# logic.net
KiCad netlist of a schematic drawn in Altium Designer
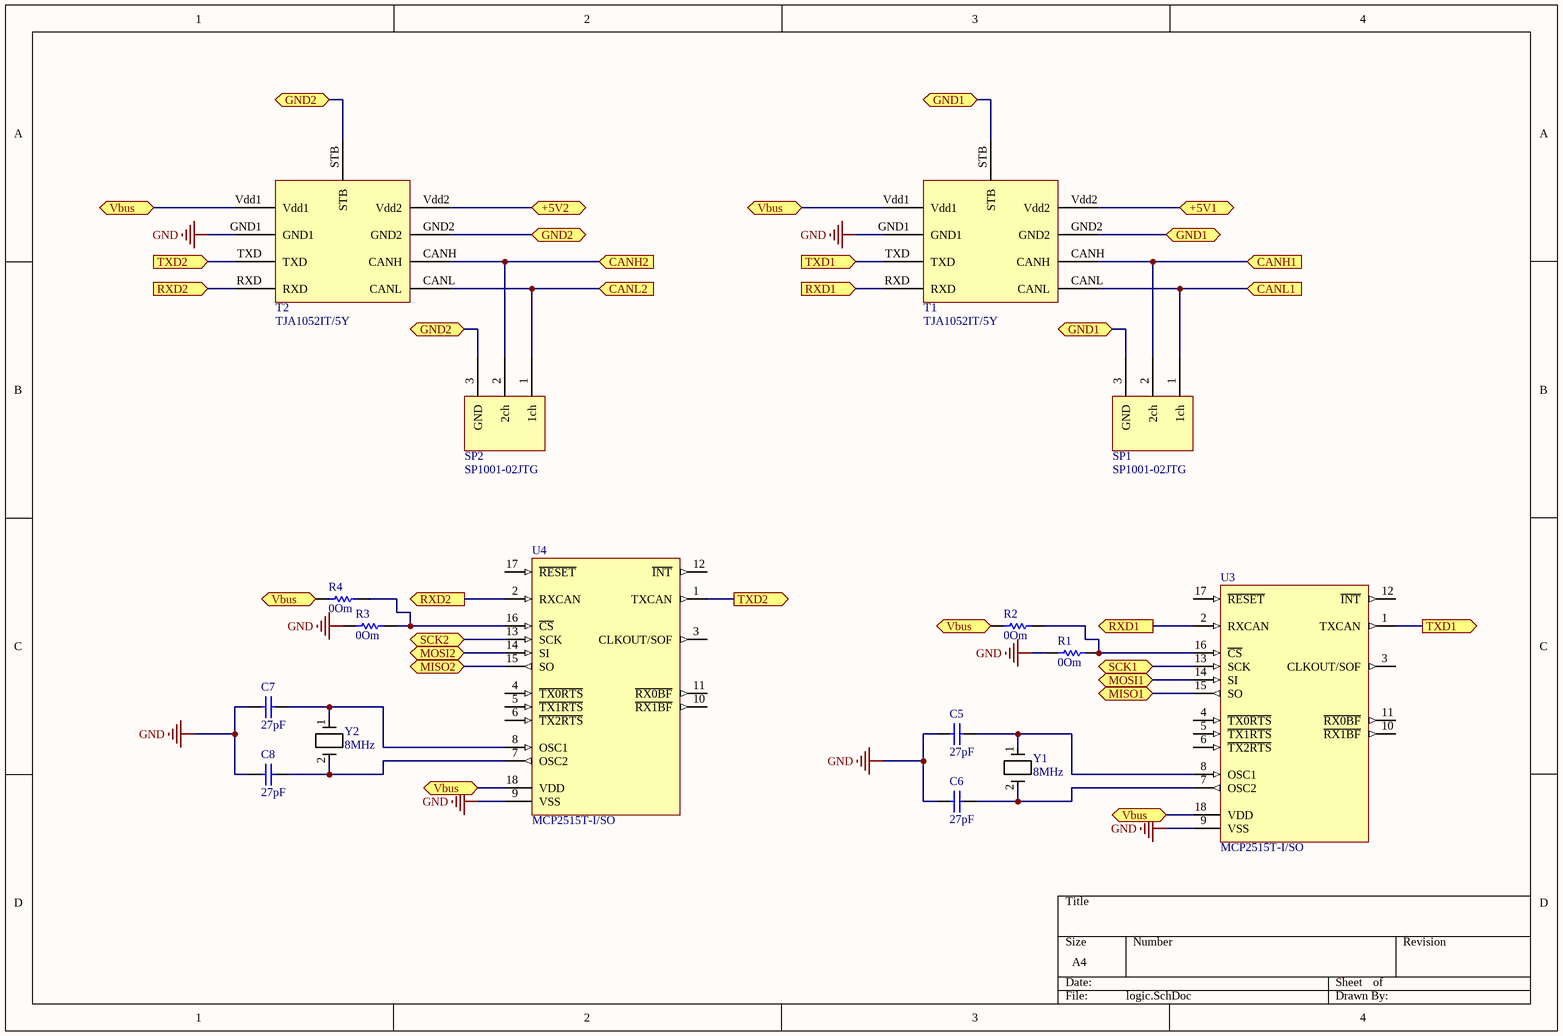
[diagram p0: logic.SchDoc]

(export (version "E")
  (design (tool "Eeschema 10.0.6"))
  (components
    (comp (ref "C5")
      (value "27pF")
      (footprint "CAPC1608X90X35ML10T15")
      (fields (field (name "MANUFACTURER") "Murata") (field (name "PART NUMBER") "GCM1885C2A101JA16D"))
      (libsource (lib "Altium Content Vault") (part "CAP"))
    )
    (comp (ref "C6")
      (value "27pF")
      (footprint "CAPC1608X90X35ML10T15")
      (fields (field (name "MANUFACTURER") "Murata") (field (name "PART NUMBER") "GCM1885C2A101JA16D"))
      (libsource (lib "Altium Content Vault") (part "CAP"))
    )
    (comp (ref "C7")
      (value "27pF")
      (footprint "CAPC1608X90X35ML10T15")
      (fields (field (name "MANUFACTURER") "Murata") (field (name "PART NUMBER") "GCM1885C2A101JA16D"))
      (libsource (lib "Altium Content Vault") (part "CAP"))
    )
    (comp (ref "C8")
      (value "27pF")
      (footprint "CAPC1608X90X35ML10T15")
      (fields (field (name "MANUFACTURER") "Murata") (field (name "PART NUMBER") "GCM1885C2A101JA16D"))
      (libsource (lib "Altium Content Vault") (part "CAP"))
    )
    (comp (ref "R1")
      (value "0Om")
      (footprint "RESC1608X55X30ML20T10")
      (fields (field (name "PART NUMBER") "RK73H1JTTD5101F") (field (name "MANUFACTURER") "KOA Speer"))
      (libsource (lib "Altium Content Vault") (part "RES"))
    )
    (comp (ref "R2")
      (value "0Om")
      (footprint "RESC1608X55X30ML20T10")
      (fields (field (name "PART NUMBER") "RK73H1JTTD5101F") (field (name "MANUFACTURER") "KOA Speer"))
      (libsource (lib "Altium Content Vault") (part "RES"))
    )
    (comp (ref "R3")
      (value "0Om")
      (footprint "RESC1608X55X30ML20T10")
      (fields (field (name "PART NUMBER") "RK73H1JTTD5101F") (field (name "MANUFACTURER") "KOA Speer"))
      (libsource (lib "Altium Content Vault") (part "RES"))
    )
    (comp (ref "R4")
      (value "0Om")
      (footprint "RESC1608X55X30ML20T10")
      (fields (field (name "PART NUMBER") "RK73H1JTTD5101F") (field (name "MANUFACTURER") "KOA Speer"))
      (libsource (lib "Altium Content Vault") (part "RES"))
    )
    (comp (ref "SP1")
      (value "SP1001-02JTG")
      (footprint "SC70-3")
      (libsource (lib "lib") (part "SP1001-02JTG"))
    )
    (comp (ref "SP2")
      (value "SP1001-02JTG")
      (footprint "SC70-3")
      (libsource (lib "lib") (part "SP1001-02JTG"))
    )
    (comp (ref "T1")
      (value "TJA1052IT/5Y")
      (footprint "TJA1052")
      (libsource (lib "lib") (part "TJA1052IT/5Y"))
    )
    (comp (ref "T2")
      (value "TJA1052IT/5Y")
      (footprint "TJA1052")
      (libsource (lib "lib") (part "TJA1052IT/5Y"))
    )
    (comp (ref "U3")
      (value "MCP2515T-I/SO")
      (footprint "SOIC-SO18_N")
      (description "Stand-Alone CAN Controller With SPI Interface, 18-Pin SOIC, Industrial Temperature, Tape and Reel")
      (libsource (lib "Altium Content Vault") (part "COM-CAN-MCP2515-18"))
    )
    (comp (ref "U4")
      (value "MCP2515T-I/SO")
      (footprint "SOIC-SO18_N")
      (description "Stand-Alone CAN Controller With SPI Interface, 18-Pin SOIC, Industrial Temperature, Tape and Reel")
      (libsource (lib "Altium Content Vault") (part "COM-CAN-MCP2515-18"))
    )
    (comp (ref "Y1")
      (value "8MHz")
      (footprint "SMD-5032_2P")
      (libsource (lib "lib") (part "SMD-5032_2P resonator"))
    )
    (comp (ref "Y2")
      (value "8MHz")
      (footprint "SMD-5032_2P")
      (libsource (lib "lib") (part "SMD-5032_2P resonator"))
    )
  )
  (nets
    (net (code "1") (name "/+5V1") (class "Default")
      (node (ref "T1") (pin "Vdd2") (pinfunction "Vdd2_Vdd2") (pintype "passive"))
    )
    (net (code "2") (name "/+5V2") (class "Default")
      (node (ref "T2") (pin "Vdd2") (pinfunction "Vdd2_Vdd2") (pintype "passive"))
    )
    (net (code "3") (name "/CANH1") (class "Default")
      (node (ref "SP1") (pin "2") (pinfunction "2ch_2") (pintype "passive"))
      (node (ref "T1") (pin "CANH") (pinfunction "CANH_CANH") (pintype "passive"))
    )
    (net (code "4") (name "/CANH2") (class "Default")
      (node (ref "SP2") (pin "2") (pinfunction "2ch_2") (pintype "passive"))
      (node (ref "T2") (pin "CANH") (pinfunction "CANH_CANH") (pintype "passive"))
    )
    (net (code "5") (name "/CANL1") (class "Default")
      (node (ref "SP1") (pin "1") (pinfunction "1ch_1") (pintype "passive"))
      (node (ref "T1") (pin "CANL") (pinfunction "CANL_CANL") (pintype "passive"))
    )
    (net (code "6") (name "/CANL2") (class "Default")
      (node (ref "SP2") (pin "1") (pinfunction "1ch_1") (pintype "passive"))
      (node (ref "T2") (pin "CANL") (pinfunction "CANL_CANL") (pintype "passive"))
    )
    (net (code "7") (name "/GND1") (class "Default")
      (node (ref "SP1") (pin "3") (pinfunction "GND_3") (pintype "passive"))
      (node (ref "T1") (pin "GND2") (pinfunction "GND2_GND2") (pintype "passive"))
      (node (ref "T1") (pin "STB") (pinfunction "STB_STB") (pintype "passive"))
    )
    (net (code "8") (name "/GND2") (class "Default")
      (node (ref "SP2") (pin "3") (pinfunction "GND_3") (pintype "passive"))
      (node (ref "T2") (pin "GND2") (pinfunction "GND2_GND2") (pintype "passive"))
      (node (ref "T2") (pin "STB") (pinfunction "STB_STB") (pintype "passive"))
    )
    (net (code "9") (name "/MISO1") (class "Default")
      (node (ref "U3") (pin "15") (pinfunction "SO_15") (pintype "output"))
    )
    (net (code "10") (name "/MISO2") (class "Default")
      (node (ref "U4") (pin "15") (pinfunction "SO_15") (pintype "output"))
    )
    (net (code "11") (name "/MOSI1") (class "Default")
      (node (ref "U3") (pin "14") (pinfunction "SI_14") (pintype "input"))
    )
    (net (code "12") (name "/MOSI2") (class "Default")
      (node (ref "U4") (pin "14") (pinfunction "SI_14") (pintype "input"))
    )
    (net (code "13") (name "/RXD1") (class "Default")
      (node (ref "T1") (pin "RXD") (pinfunction "RXD_RXD") (pintype "passive"))
      (node (ref "U3") (pin "2") (pinfunction "RXCAN_2") (pintype "input"))
    )
    (net (code "14") (name "/RXD2") (class "Default")
      (node (ref "T2") (pin "RXD") (pinfunction "RXD_RXD") (pintype "passive"))
      (node (ref "U4") (pin "2") (pinfunction "RXCAN_2") (pintype "input"))
    )
    (net (code "15") (name "/SCK1") (class "Default")
      (node (ref "U3") (pin "13") (pinfunction "SCK_13") (pintype "input"))
    )
    (net (code "16") (name "/SCK2") (class "Default")
      (node (ref "U4") (pin "13") (pinfunction "SCK_13") (pintype "input"))
    )
    (net (code "17") (name "/TXD1") (class "Default")
      (node (ref "T1") (pin "TXD") (pinfunction "TXD_TXD") (pintype "passive"))
      (node (ref "U3") (pin "1") (pinfunction "TXCAN_1") (pintype "output"))
    )
    (net (code "18") (name "/TXD2") (class "Default")
      (node (ref "T2") (pin "TXD") (pinfunction "TXD_TXD") (pintype "passive"))
      (node (ref "U4") (pin "1") (pinfunction "TXCAN_1") (pintype "output"))
    )
    (net (code "19") (name "/Vbus") (class "Default")
      (node (ref "R2") (pin "1") (pinfunction "1_1") (pintype "passive"))
      (node (ref "R4") (pin "1") (pinfunction "1_1") (pintype "passive"))
      (node (ref "T1") (pin "Vdd1") (pinfunction "Vdd1_Vdd1") (pintype "passive"))
      (node (ref "T2") (pin "Vdd1") (pinfunction "Vdd1_Vdd1") (pintype "passive"))
      (node (ref "U3") (pin "18") (pinfunction "VDD_18") (pintype "power_in"))
      (node (ref "U4") (pin "18") (pinfunction "VDD_18") (pintype "power_in"))
    )
    (net (code "20") (name "GND") (class "Default")
      (node (ref "C5") (pin "1") (pinfunction "1_1") (pintype "passive"))
      (node (ref "C6") (pin "1") (pinfunction "1_1") (pintype "passive"))
      (node (ref "C7") (pin "1") (pinfunction "1_1") (pintype "passive"))
      (node (ref "C8") (pin "1") (pinfunction "1_1") (pintype "passive"))
      (node (ref "R1") (pin "1") (pinfunction "1_1") (pintype "passive"))
      (node (ref "R3") (pin "1") (pinfunction "1_1") (pintype "passive"))
      (node (ref "T1") (pin "GND1") (pinfunction "GND1_GND1") (pintype "passive"))
      (node (ref "T2") (pin "GND1") (pinfunction "GND1_GND1") (pintype "passive"))
      (node (ref "U3") (pin "9") (pinfunction "VSS_9") (pintype "power_in"))
      (node (ref "U4") (pin "9") (pinfunction "VSS_9") (pintype "power_in"))
    )
    (net (code "21") (name "Net-(U3-OSC1)") (class "Default")
      (node (ref "C5") (pin "2") (pinfunction "2_2") (pintype "passive"))
      (node (ref "U3") (pin "8") (pinfunction "OSC1_8") (pintype "input"))
      (node (ref "Y1") (pin "1") (pintype "passive"))
    )
    (net (code "22") (name "Net-(U3-OSC2)") (class "Default")
      (node (ref "C6") (pin "2") (pinfunction "2_2") (pintype "passive"))
      (node (ref "U3") (pin "7") (pinfunction "OSC2_7") (pintype "output"))
      (node (ref "Y1") (pin "2") (pintype "passive"))
    )
    (net (code "23") (name "Net-(U3-~{CS})") (class "Default")
      (node (ref "R1") (pin "2") (pinfunction "2_2") (pintype "passive"))
      (node (ref "R2") (pin "2") (pinfunction "2_2") (pintype "passive"))
      (node (ref "U3") (pin "16") (pinfunction "~{CS}_16") (pintype "input"))
    )
    (net (code "24") (name "Net-(U4-OSC1)") (class "Default")
      (node (ref "C7") (pin "2") (pinfunction "2_2") (pintype "passive"))
      (node (ref "U4") (pin "8") (pinfunction "OSC1_8") (pintype "input"))
      (node (ref "Y2") (pin "1") (pintype "passive"))
    )
    (net (code "25") (name "Net-(U4-OSC2)") (class "Default")
      (node (ref "C8") (pin "2") (pinfunction "2_2") (pintype "passive"))
      (node (ref "U4") (pin "7") (pinfunction "OSC2_7") (pintype "output"))
      (node (ref "Y2") (pin "2") (pintype "passive"))
    )
    (net (code "26") (name "Net-(U4-~{CS})") (class "Default")
      (node (ref "R3") (pin "2") (pinfunction "2_2") (pintype "passive"))
      (node (ref "R4") (pin "2") (pinfunction "2_2") (pintype "passive"))
      (node (ref "U4") (pin "16") (pinfunction "~{CS}_16") (pintype "input"))
    )
    (net (code "27") (name "unconnected-(U3-CLKOUT{slash}SOF-Pad3)") (class "Default")
      (node (ref "U3") (pin "3") (pinfunction "CLKOUT/SOF_3") (pintype "output"))
    )
    (net (code "28") (name "unconnected-(U3-~{INT}-Pad12)") (class "Default")
      (node (ref "U3") (pin "12") (pinfunction "~{INT}_12") (pintype "output"))
    )
    (net (code "29") (name "unconnected-(U3-~{RESET}-Pad17)") (class "Default")
      (node (ref "U3") (pin "17") (pinfunction "~{RESET}_17") (pintype "input"))
    )
    (net (code "30") (name "unconnected-(U3-~{RX0BF}-Pad11)") (class "Default")
      (node (ref "U3") (pin "11") (pinfunction "~{RX0BF}_11") (pintype "output"))
    )
    (net (code "31") (name "unconnected-(U3-~{RX1BF}-Pad10)") (class "Default")
      (node (ref "U3") (pin "10") (pinfunction "~{RX1BF}_10") (pintype "output"))
    )
    (net (code "32") (name "unconnected-(U3-~{TX0RTS}-Pad4)") (class "Default")
      (node (ref "U3") (pin "4") (pinfunction "~{TX0RTS}_4") (pintype "input"))
    )
    (net (code "33") (name "unconnected-(U3-~{TX1RTS}-Pad5)") (class "Default")
      (node (ref "U3") (pin "5") (pinfunction "~{TX1RTS}_5") (pintype "input"))
    )
    (net (code "34") (name "unconnected-(U3-~{TX2RTS}-Pad6)") (class "Default")
      (node (ref "U3") (pin "6") (pinfunction "~{TX2RTS}_6") (pintype "input"))
    )
    (net (code "35") (name "unconnected-(U4-CLKOUT{slash}SOF-Pad3)") (class "Default")
      (node (ref "U4") (pin "3") (pinfunction "CLKOUT/SOF_3") (pintype "output"))
    )
    (net (code "36") (name "unconnected-(U4-~{INT}-Pad12)") (class "Default")
      (node (ref "U4") (pin "12") (pinfunction "~{INT}_12") (pintype "output"))
    )
    (net (code "37") (name "unconnected-(U4-~{RESET}-Pad17)") (class "Default")
      (node (ref "U4") (pin "17") (pinfunction "~{RESET}_17") (pintype "input"))
    )
    (net (code "38") (name "unconnected-(U4-~{RX0BF}-Pad11)") (class "Default")
      (node (ref "U4") (pin "11") (pinfunction "~{RX0BF}_11") (pintype "output"))
    )
    (net (code "39") (name "unconnected-(U4-~{RX1BF}-Pad10)") (class "Default")
      (node (ref "U4") (pin "10") (pinfunction "~{RX1BF}_10") (pintype "output"))
    )
    (net (code "40") (name "unconnected-(U4-~{TX0RTS}-Pad4)") (class "Default")
      (node (ref "U4") (pin "4") (pinfunction "~{TX0RTS}_4") (pintype "input"))
    )
    (net (code "41") (name "unconnected-(U4-~{TX1RTS}-Pad5)") (class "Default")
      (node (ref "U4") (pin "5") (pinfunction "~{TX1RTS}_5") (pintype "input"))
    )
    (net (code "42") (name "unconnected-(U4-~{TX2RTS}-Pad6)") (class "Default")
      (node (ref "U4") (pin "6") (pinfunction "~{TX2RTS}_6") (pintype "input"))
    )
  )
)
